# Puzzle_Circular_LED_v0_9b.net
KiCad netlist of a schematic drawn in EAGLE
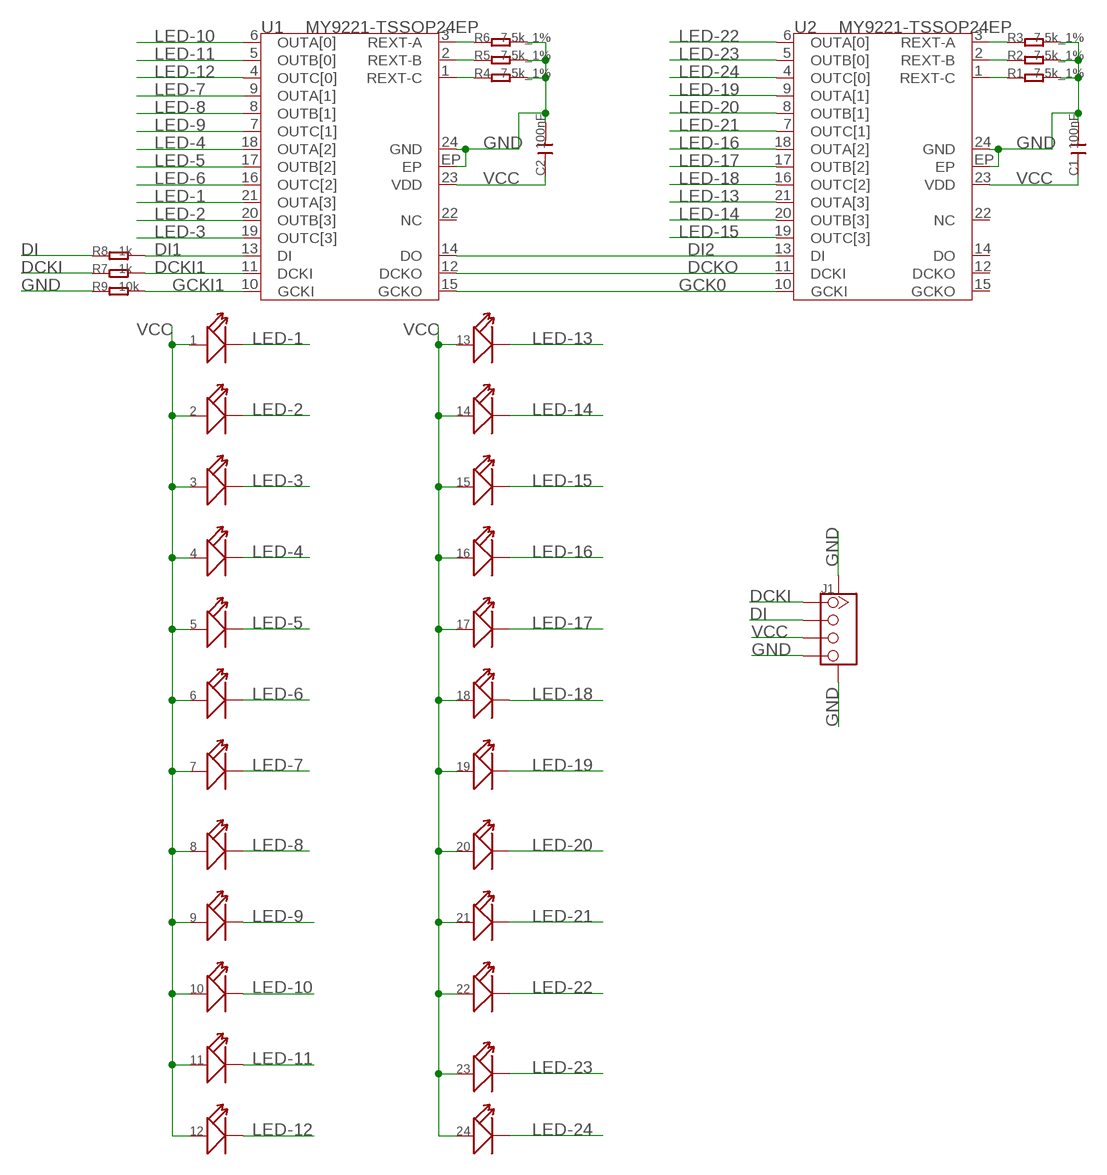
[diagram p0: schematic, sheet 1]

(export (version "E")
  (design (tool "Eeschema 10.0.6"))
  (components
    (comp (ref "1")
      (value "LED'1206'")
      (footprint "eagle-import:LED-1206")
      (libsource (lib "eagle-import") (part "LED'1206'"))
    )
    (comp (ref "2")
      (value "LED'1206'")
      (footprint "eagle-import:LED-1206")
      (libsource (lib "eagle-import") (part "LED'1206'"))
    )
    (comp (ref "3")
      (value "LED'1206'")
      (footprint "eagle-import:LED-1206")
      (libsource (lib "eagle-import") (part "LED'1206'"))
    )
    (comp (ref "4")
      (value "LED'1206'")
      (footprint "eagle-import:LED-1206")
      (libsource (lib "eagle-import") (part "LED'1206'"))
    )
    (comp (ref "5")
      (value "LED'1206'")
      (footprint "eagle-import:LED-1206")
      (libsource (lib "eagle-import") (part "LED'1206'"))
    )
    (comp (ref "6")
      (value "LED'1206'")
      (footprint "eagle-import:LED-1206")
      (libsource (lib "eagle-import") (part "LED'1206'"))
    )
    (comp (ref "7")
      (value "LED'1206'")
      (footprint "eagle-import:LED-1206")
      (libsource (lib "eagle-import") (part "LED'1206'"))
    )
    (comp (ref "8")
      (value "LED'1206'")
      (footprint "eagle-import:LED-1206")
      (libsource (lib "eagle-import") (part "LED'1206'"))
    )
    (comp (ref "9")
      (value "LED'1206'")
      (footprint "eagle-import:LED-1206")
      (libsource (lib "eagle-import") (part "LED'1206'"))
    )
    (comp (ref "10")
      (value "LED'1206'")
      (footprint "eagle-import:LED-1206")
      (libsource (lib "eagle-import") (part "LED'1206'"))
    )
    (comp (ref "11")
      (value "LED'1206'")
      (footprint "eagle-import:LED-1206")
      (libsource (lib "eagle-import") (part "LED'1206'"))
    )
    (comp (ref "12")
      (value "LED'1206'")
      (footprint "eagle-import:LED-1206")
      (libsource (lib "eagle-import") (part "LED'1206'"))
    )
    (comp (ref "13")
      (value "LED'1206'")
      (footprint "eagle-import:LED-1206")
      (libsource (lib "eagle-import") (part "LED'1206'"))
    )
    (comp (ref "14")
      (value "LED'1206'")
      (footprint "eagle-import:LED-1206")
      (libsource (lib "eagle-import") (part "LED'1206'"))
    )
    (comp (ref "15")
      (value "LED'1206'")
      (footprint "eagle-import:LED-1206")
      (libsource (lib "eagle-import") (part "LED'1206'"))
    )
    (comp (ref "16")
      (value "LED'1206'")
      (footprint "eagle-import:LED-1206")
      (libsource (lib "eagle-import") (part "LED'1206'"))
    )
    (comp (ref "17")
      (value "LED'1206'")
      (footprint "eagle-import:LED-1206")
      (libsource (lib "eagle-import") (part "LED'1206'"))
    )
    (comp (ref "18")
      (value "LED'1206'")
      (footprint "eagle-import:LED-1206")
      (libsource (lib "eagle-import") (part "LED'1206'"))
    )
    (comp (ref "19")
      (value "LED'1206'")
      (footprint "eagle-import:LED-1206")
      (libsource (lib "eagle-import") (part "LED'1206'"))
    )
    (comp (ref "20")
      (value "LED'1206'")
      (footprint "eagle-import:LED-1206")
      (libsource (lib "eagle-import") (part "LED'1206'"))
    )
    (comp (ref "21")
      (value "LED'1206'")
      (footprint "eagle-import:LED-1206")
      (libsource (lib "eagle-import") (part "LED'1206'"))
    )
    (comp (ref "22")
      (value "LED'1206'")
      (footprint "eagle-import:LED-1206")
      (libsource (lib "eagle-import") (part "LED'1206'"))
    )
    (comp (ref "23")
      (value "LED'1206'")
      (footprint "eagle-import:LED-1206")
      (libsource (lib "eagle-import") (part "LED'1206'"))
    )
    (comp (ref "24")
      (value "LED'1206'")
      (footprint "eagle-import:LED-1206")
      (libsource (lib "eagle-import") (part "LED'1206'"))
    )
    (comp (ref "C1")
      (value "100nF")
      (footprint "eagle-import:C0603")
      (libsource (lib "eagle-import") (part "C-0603"))
    )
    (comp (ref "C2")
      (value "100nF")
      (footprint "eagle-import:C0603")
      (libsource (lib "eagle-import") (part "C-0603"))
    )
    (comp (ref "J1")
      (value "TWIG-4P-2.0-SMD-FEMALE-REINFORCE'90D'")
      (footprint "eagle-import:4P-SMD-2.0-90D")
      (libsource (lib "eagle-import") (part "TWIG-4P-2.0-SMD-FEMALE-REINFORCE'90D'"))
    )
    (comp (ref "R1")
      (value "7.5k_1%")
      (footprint "eagle-import:R0603")
      (libsource (lib "eagle-import") (part "R-0603"))
    )
    (comp (ref "R2")
      (value "7.5k_1%")
      (footprint "eagle-import:R0603")
      (libsource (lib "eagle-import") (part "R-0603"))
    )
    (comp (ref "R3")
      (value "7.5k_1%")
      (footprint "eagle-import:R0603")
      (libsource (lib "eagle-import") (part "R-0603"))
    )
    (comp (ref "R4")
      (value "7.5k_1%")
      (footprint "eagle-import:R0603")
      (libsource (lib "eagle-import") (part "R-0603"))
    )
    (comp (ref "R5")
      (value "7.5k_1%")
      (footprint "eagle-import:R0603")
      (libsource (lib "eagle-import") (part "R-0603"))
    )
    (comp (ref "R6")
      (value "7.5k_1%")
      (footprint "eagle-import:R0603")
      (libsource (lib "eagle-import") (part "R-0603"))
    )
    (comp (ref "R7")
      (value "1k")
      (footprint "eagle-import:R0603")
      (libsource (lib "eagle-import") (part "R-0603"))
    )
    (comp (ref "R8")
      (value "1k")
      (footprint "eagle-import:R0603")
      (libsource (lib "eagle-import") (part "R-0603"))
    )
    (comp (ref "R9")
      (value "10k")
      (footprint "eagle-import:R0603")
      (libsource (lib "eagle-import") (part "R-0603"))
    )
    (comp (ref "U1")
      (value "MY9221-TSSOP24EP")
      (footprint "eagle-import:TSSOP24EP")
      (libsource (lib "eagle-import") (part "MY9221-TSSOP24EP"))
    )
    (comp (ref "U2")
      (value "MY9221-TSSOP24EP")
      (footprint "eagle-import:TSSOP24EP")
      (libsource (lib "eagle-import") (part "MY9221-TSSOP24EP"))
    )
  )
  (nets
    (net (code "1") (name "/DCKI") (class "Default")
      (node (ref "J1") (pin "1") (pinfunction "1_1") (pintype "bidirectional"))
      (node (ref "R7") (pin "1") (pinfunction "1_1") (pintype "passive"))
    )
    (net (code "2") (name "/DCKI1") (class "Default")
      (node (ref "R7") (pin "2") (pinfunction "2_2") (pintype "passive"))
      (node (ref "U1") (pin "11") (pinfunction "DCKI_11") (pintype "bidirectional"))
    )
    (net (code "3") (name "/DCKO") (class "Default")
      (node (ref "U1") (pin "12") (pinfunction "DCKO_12") (pintype "bidirectional"))
      (node (ref "U2") (pin "11") (pinfunction "DCKI_11") (pintype "bidirectional"))
    )
    (net (code "4") (name "/DI") (class "Default")
      (node (ref "J1") (pin "2") (pinfunction "2_2") (pintype "bidirectional"))
      (node (ref "R8") (pin "1") (pinfunction "1_1") (pintype "passive"))
    )
    (net (code "5") (name "/DI1") (class "Default")
      (node (ref "R8") (pin "2") (pinfunction "2_2") (pintype "passive"))
      (node (ref "U1") (pin "13") (pinfunction "DI_13") (pintype "bidirectional"))
    )
    (net (code "6") (name "/DI2") (class "Default")
      (node (ref "U1") (pin "14") (pinfunction "DO_14") (pintype "bidirectional"))
      (node (ref "U2") (pin "13") (pinfunction "DI_13") (pintype "bidirectional"))
    )
    (net (code "7") (name "/GCK0") (class "Default")
      (node (ref "U1") (pin "15") (pinfunction "GCKO_15") (pintype "bidirectional"))
      (node (ref "U2") (pin "10") (pinfunction "GCKI_10") (pintype "bidirectional"))
    )
    (net (code "8") (name "/GCKI1") (class "Default")
      (node (ref "R9") (pin "2") (pinfunction "2_2") (pintype "passive"))
      (node (ref "U1") (pin "10") (pinfunction "GCKI_10") (pintype "bidirectional"))
    )
    (net (code "9") (name "/GND") (class "Default")
      (node (ref "C1") (pin "2") (pinfunction "2_2") (pintype "passive"))
      (node (ref "C2") (pin "2") (pinfunction "2_2") (pintype "passive"))
      (node (ref "J1") (pin "4") (pinfunction "4_4") (pintype "bidirectional"))
      (node (ref "J1") (pin "SS1") (pinfunction "SS1_SS1") (pintype "bidirectional"))
      (node (ref "J1") (pin "SS2") (pinfunction "SS2_SS2") (pintype "bidirectional"))
      (node (ref "R1") (pin "2") (pinfunction "2_2") (pintype "passive"))
      (node (ref "R2") (pin "2") (pinfunction "2_2") (pintype "passive"))
      (node (ref "R3") (pin "2") (pinfunction "2_2") (pintype "passive"))
      (node (ref "R4") (pin "2") (pinfunction "2_2") (pintype "passive"))
      (node (ref "R5") (pin "2") (pinfunction "2_2") (pintype "passive"))
      (node (ref "R6") (pin "2") (pinfunction "2_2") (pintype "passive"))
      (node (ref "R9") (pin "1") (pinfunction "1_1") (pintype "passive"))
      (node (ref "U1") (pin "24") (pinfunction "GND_24") (pintype "power_in"))
      (node (ref "U1") (pin "EP") (pinfunction "EP_EP") (pintype "bidirectional"))
      (node (ref "U2") (pin "24") (pinfunction "GND_24") (pintype "power_in"))
      (node (ref "U2") (pin "EP") (pinfunction "EP_EP") (pintype "bidirectional"))
    )
    (net (code "10") (name "/LED-1") (class "Default")
      (node (ref "1") (pin "-") (pinfunction "-_-") (pintype "passive"))
      (node (ref "U1") (pin "21") (pinfunction "OUTA[3]_21") (pintype "bidirectional"))
    )
    (net (code "11") (name "/LED-2") (class "Default")
      (node (ref "2") (pin "-") (pinfunction "-_-") (pintype "passive"))
      (node (ref "U1") (pin "20") (pinfunction "OUTB[3]_20") (pintype "bidirectional"))
    )
    (net (code "12") (name "/LED-3") (class "Default")
      (node (ref "3") (pin "-") (pinfunction "-_-") (pintype "passive"))
      (node (ref "U1") (pin "19") (pinfunction "OUTC[3]_19") (pintype "bidirectional"))
    )
    (net (code "13") (name "/LED-4") (class "Default")
      (node (ref "4") (pin "-") (pinfunction "-_-") (pintype "passive"))
      (node (ref "U1") (pin "18") (pinfunction "OUTA[2]_18") (pintype "bidirectional"))
    )
    (net (code "14") (name "/LED-5") (class "Default")
      (node (ref "5") (pin "-") (pinfunction "-_-") (pintype "passive"))
      (node (ref "U1") (pin "17") (pinfunction "OUTB[2]_17") (pintype "bidirectional"))
    )
    (net (code "15") (name "/LED-6") (class "Default")
      (node (ref "6") (pin "-") (pinfunction "-_-") (pintype "passive"))
      (node (ref "U1") (pin "16") (pinfunction "OUTC[2]_16") (pintype "bidirectional"))
    )
    (net (code "16") (name "/LED-7") (class "Default")
      (node (ref "7") (pin "-") (pinfunction "-_-") (pintype "passive"))
      (node (ref "U1") (pin "9") (pinfunction "OUTA[1]_9") (pintype "bidirectional"))
    )
    (net (code "17") (name "/LED-8") (class "Default")
      (node (ref "8") (pin "-") (pinfunction "-_-") (pintype "passive"))
      (node (ref "U1") (pin "8") (pinfunction "OUTB[1]_8") (pintype "bidirectional"))
    )
    (net (code "18") (name "/LED-9") (class "Default")
      (node (ref "9") (pin "-") (pinfunction "-_-") (pintype "passive"))
      (node (ref "U1") (pin "7") (pinfunction "OUTC[1]_7") (pintype "bidirectional"))
    )
    (net (code "19") (name "/LED-10") (class "Default")
      (node (ref "10") (pin "-") (pinfunction "-_-") (pintype "passive"))
      (node (ref "U1") (pin "6") (pinfunction "OUTA[0]_6") (pintype "bidirectional"))
    )
    (net (code "20") (name "/LED-11") (class "Default")
      (node (ref "11") (pin "-") (pinfunction "-_-") (pintype "passive"))
      (node (ref "U1") (pin "5") (pinfunction "OUTB[0]_5") (pintype "bidirectional"))
    )
    (net (code "21") (name "/LED-12") (class "Default")
      (node (ref "12") (pin "-") (pinfunction "-_-") (pintype "passive"))
      (node (ref "U1") (pin "4") (pinfunction "OUTC[0]_4") (pintype "bidirectional"))
    )
    (net (code "22") (name "/LED-13") (class "Default")
      (node (ref "13") (pin "-") (pinfunction "-_-") (pintype "passive"))
      (node (ref "U2") (pin "21") (pinfunction "OUTA[3]_21") (pintype "bidirectional"))
    )
    (net (code "23") (name "/LED-14") (class "Default")
      (node (ref "14") (pin "-") (pinfunction "-_-") (pintype "passive"))
      (node (ref "U2") (pin "20") (pinfunction "OUTB[3]_20") (pintype "bidirectional"))
    )
    (net (code "24") (name "/LED-15") (class "Default")
      (node (ref "15") (pin "-") (pinfunction "-_-") (pintype "passive"))
      (node (ref "U2") (pin "19") (pinfunction "OUTC[3]_19") (pintype "bidirectional"))
    )
    (net (code "25") (name "/LED-16") (class "Default")
      (node (ref "16") (pin "-") (pinfunction "-_-") (pintype "passive"))
      (node (ref "U2") (pin "18") (pinfunction "OUTA[2]_18") (pintype "bidirectional"))
    )
    (net (code "26") (name "/LED-17") (class "Default")
      (node (ref "17") (pin "-") (pinfunction "-_-") (pintype "passive"))
      (node (ref "U2") (pin "17") (pinfunction "OUTB[2]_17") (pintype "bidirectional"))
    )
    (net (code "27") (name "/LED-18") (class "Default")
      (node (ref "18") (pin "-") (pinfunction "-_-") (pintype "passive"))
      (node (ref "U2") (pin "16") (pinfunction "OUTC[2]_16") (pintype "bidirectional"))
    )
    (net (code "28") (name "/LED-19") (class "Default")
      (node (ref "19") (pin "-") (pinfunction "-_-") (pintype "passive"))
      (node (ref "U2") (pin "9") (pinfunction "OUTA[1]_9") (pintype "bidirectional"))
    )
    (net (code "29") (name "/LED-20") (class "Default")
      (node (ref "20") (pin "-") (pinfunction "-_-") (pintype "passive"))
      (node (ref "U2") (pin "8") (pinfunction "OUTB[1]_8") (pintype "bidirectional"))
    )
    (net (code "30") (name "/LED-21") (class "Default")
      (node (ref "21") (pin "-") (pinfunction "-_-") (pintype "passive"))
      (node (ref "U2") (pin "7") (pinfunction "OUTC[1]_7") (pintype "bidirectional"))
    )
    (net (code "31") (name "/LED-22") (class "Default")
      (node (ref "22") (pin "-") (pinfunction "-_-") (pintype "passive"))
      (node (ref "U2") (pin "6") (pinfunction "OUTA[0]_6") (pintype "bidirectional"))
    )
    (net (code "32") (name "/LED-23") (class "Default")
      (node (ref "23") (pin "-") (pinfunction "-_-") (pintype "passive"))
      (node (ref "U2") (pin "5") (pinfunction "OUTB[0]_5") (pintype "bidirectional"))
    )
    (net (code "33") (name "/LED-24") (class "Default")
      (node (ref "24") (pin "-") (pinfunction "-_-") (pintype "passive"))
      (node (ref "U2") (pin "4") (pinfunction "OUTC[0]_4") (pintype "bidirectional"))
    )
    (net (code "34") (name "/VCC") (class "Default")
      (node (ref "1") (pin "+") (pinfunction "+_+") (pintype "passive"))
      (node (ref "10") (pin "+") (pinfunction "+_+") (pintype "passive"))
      (node (ref "11") (pin "+") (pinfunction "+_+") (pintype "passive"))
      (node (ref "12") (pin "+") (pinfunction "+_+") (pintype "passive"))
      (node (ref "13") (pin "+") (pinfunction "+_+") (pintype "passive"))
      (node (ref "14") (pin "+") (pinfunction "+_+") (pintype "passive"))
      (node (ref "15") (pin "+") (pinfunction "+_+") (pintype "passive"))
      (node (ref "16") (pin "+") (pinfunction "+_+") (pintype "passive"))
      (node (ref "17") (pin "+") (pinfunction "+_+") (pintype "passive"))
      (node (ref "18") (pin "+") (pinfunction "+_+") (pintype "passive"))
      (node (ref "19") (pin "+") (pinfunction "+_+") (pintype "passive"))
      (node (ref "2") (pin "+") (pinfunction "+_+") (pintype "passive"))
      (node (ref "20") (pin "+") (pinfunction "+_+") (pintype "passive"))
      (node (ref "21") (pin "+") (pinfunction "+_+") (pintype "passive"))
      (node (ref "22") (pin "+") (pinfunction "+_+") (pintype "passive"))
      (node (ref "23") (pin "+") (pinfunction "+_+") (pintype "passive"))
      (node (ref "24") (pin "+") (pinfunction "+_+") (pintype "passive"))
      (node (ref "3") (pin "+") (pinfunction "+_+") (pintype "passive"))
      (node (ref "4") (pin "+") (pinfunction "+_+") (pintype "passive"))
      (node (ref "5") (pin "+") (pinfunction "+_+") (pintype "passive"))
      (node (ref "6") (pin "+") (pinfunction "+_+") (pintype "passive"))
      (node (ref "7") (pin "+") (pinfunction "+_+") (pintype "passive"))
      (node (ref "8") (pin "+") (pinfunction "+_+") (pintype "passive"))
      (node (ref "9") (pin "+") (pinfunction "+_+") (pintype "passive"))
      (node (ref "C1") (pin "1") (pinfunction "1_1") (pintype "passive"))
      (node (ref "C2") (pin "1") (pinfunction "1_1") (pintype "passive"))
      (node (ref "J1") (pin "3") (pinfunction "3_3") (pintype "bidirectional"))
      (node (ref "U1") (pin "23") (pinfunction "VDD_23") (pintype "power_in"))
      (node (ref "U2") (pin "23") (pinfunction "VDD_23") (pintype "power_in"))
    )
    (net (code "35") (name "Net-(U1-REXT-A)") (class "Default")
      (node (ref "R6") (pin "1") (pinfunction "1_1") (pintype "passive"))
      (node (ref "U1") (pin "3") (pinfunction "REXT-A_3") (pintype "bidirectional"))
    )
    (net (code "36") (name "Net-(U1-REXT-B)") (class "Default")
      (node (ref "R5") (pin "1") (pinfunction "1_1") (pintype "passive"))
      (node (ref "U1") (pin "2") (pinfunction "REXT-B_2") (pintype "bidirectional"))
    )
    (net (code "37") (name "Net-(U1-REXT-C)") (class "Default")
      (node (ref "R4") (pin "1") (pinfunction "1_1") (pintype "passive"))
      (node (ref "U1") (pin "1") (pinfunction "REXT-C_1") (pintype "bidirectional"))
    )
    (net (code "38") (name "Net-(U2-REXT-A)") (class "Default")
      (node (ref "R3") (pin "1") (pinfunction "1_1") (pintype "passive"))
      (node (ref "U2") (pin "3") (pinfunction "REXT-A_3") (pintype "bidirectional"))
    )
    (net (code "39") (name "Net-(U2-REXT-B)") (class "Default")
      (node (ref "R2") (pin "1") (pinfunction "1_1") (pintype "passive"))
      (node (ref "U2") (pin "2") (pinfunction "REXT-B_2") (pintype "bidirectional"))
    )
    (net (code "40") (name "Net-(U2-REXT-C)") (class "Default")
      (node (ref "R1") (pin "1") (pinfunction "1_1") (pintype "passive"))
      (node (ref "U2") (pin "1") (pinfunction "REXT-C_1") (pintype "bidirectional"))
    )
    (net (code "41") (name "unconnected-(U1-NC-Pad22)") (class "Default")
      (node (ref "U1") (pin "22") (pinfunction "NC_22") (pintype "bidirectional"))
    )
    (net (code "42") (name "unconnected-(U2-DCKO-Pad12)") (class "Default")
      (node (ref "U2") (pin "12") (pinfunction "DCKO_12") (pintype "bidirectional"))
    )
    (net (code "43") (name "unconnected-(U2-DO-Pad14)") (class "Default")
      (node (ref "U2") (pin "14") (pinfunction "DO_14") (pintype "bidirectional"))
    )
    (net (code "44") (name "unconnected-(U2-GCKO-Pad15)") (class "Default")
      (node (ref "U2") (pin "15") (pinfunction "GCKO_15") (pintype "bidirectional"))
    )
    (net (code "45") (name "unconnected-(U2-NC-Pad22)") (class "Default")
      (node (ref "U2") (pin "22") (pinfunction "NC_22") (pintype "bidirectional"))
    )
  )
)
